# 6_VibrationMotor.net
KiCad netlist of a schematic drawn in Altium Designer
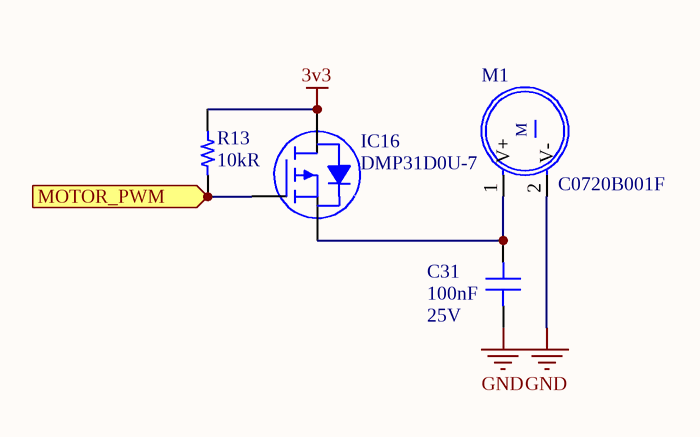
[diagram p0: [6] VibrationMotor.SchDoc]

(export (version "E")
  (design (tool "Eeschema 10.0.6"))
  (components
    (comp (ref "C31")
      (value "100nF")
      (footprint "CAP 0402/1005")
      (description "Cap Ceramic 0.1uF 25V X5R 10% Pad SMD 0402 85°C T/R / Multi Layer Ceramic Capacitor (MLCC)")
      (fields
        (field (name "MANUFACTURER") "Samsung")
        (field (name "MANUFACTURER PART NUMBER") "CL05A104KA5NNNC")
        (field (name "VOLTAGE RATING (DC)") "25V")
      )
      (libsource (lib "yildizIoT Library") (part "Capacitor - Ceramic"))
    )
    (comp (ref "IC16")
      (value "DMP31D0U-7")
      (footprint "DIODES SOT-23-3")
      (description "MOSFET P-CH 30V 530MA SOT23")
      (fields (field (name "MANUFACTURER") "Diodes Incorporated"))
      (libsource (lib "Celestial Altium Library - altium_library") (part "DIODES MOSFET P-CH SOT-23-3"))
    )
    (comp (ref "M1")
      (value "C0720B001F")
      (footprint "VYBRONICS C0720B001F")
      (description "DC Motor Vibration, ERM 10000 RPM 3VDC")
      (libsource (lib "yildizIoT Library") (part "VYBRONICS C0720B001F"))
    )
    (comp (ref "R13")
      (value "10kR")
      (footprint "RES 0402/1005")
      (description "Res Thick Film 0402 10K Ohm 1% 0.063W(1/16W) ±100ppm/C Pad SMD Automotive T/R")
      (fields
        (field (name "MANUFACTURER") "Stackpole Electronics")
        (field (name "MANUFACTURER PART NUMBER") "RMCF0402FT10K0")
      )
      (libsource (lib "yildizIoT Library") (part "Resistor_Chip"))
    )
  )
  (nets
    (net (code "1") (name "/MOTOR_PWM") (class "Default")
      (node (ref "IC16") (pin "1") (pinfunction "G_1") (pintype "passive"))
      (node (ref "R13") (pin "1") (pinfunction "1_1") (pintype "passive"))
    )
    (net (code "2") (name "3v3") (class "Default")
      (node (ref "IC16") (pin "3") (pinfunction "D_3") (pintype "passive"))
      (node (ref "R13") (pin "2") (pinfunction "2_2") (pintype "passive"))
    )
    (net (code "3") (name "GND") (class "Default")
      (node (ref "C31") (pin "1") (pinfunction "1_1") (pintype "passive"))
      (node (ref "M1") (pin "2") (pinfunction "V-_2") (pintype "power_in"))
    )
    (net (code "4") (name "Net-(IC16-S)") (class "Default")
      (node (ref "C31") (pin "2") (pinfunction "2_2") (pintype "passive"))
      (node (ref "IC16") (pin "2") (pinfunction "S_2") (pintype "passive"))
      (node (ref "M1") (pin "1") (pinfunction "V+_1") (pintype "power_in"))
    )
  )
)
